# uctester.net
KiCad netlist of a schematic drawn in EAGLE
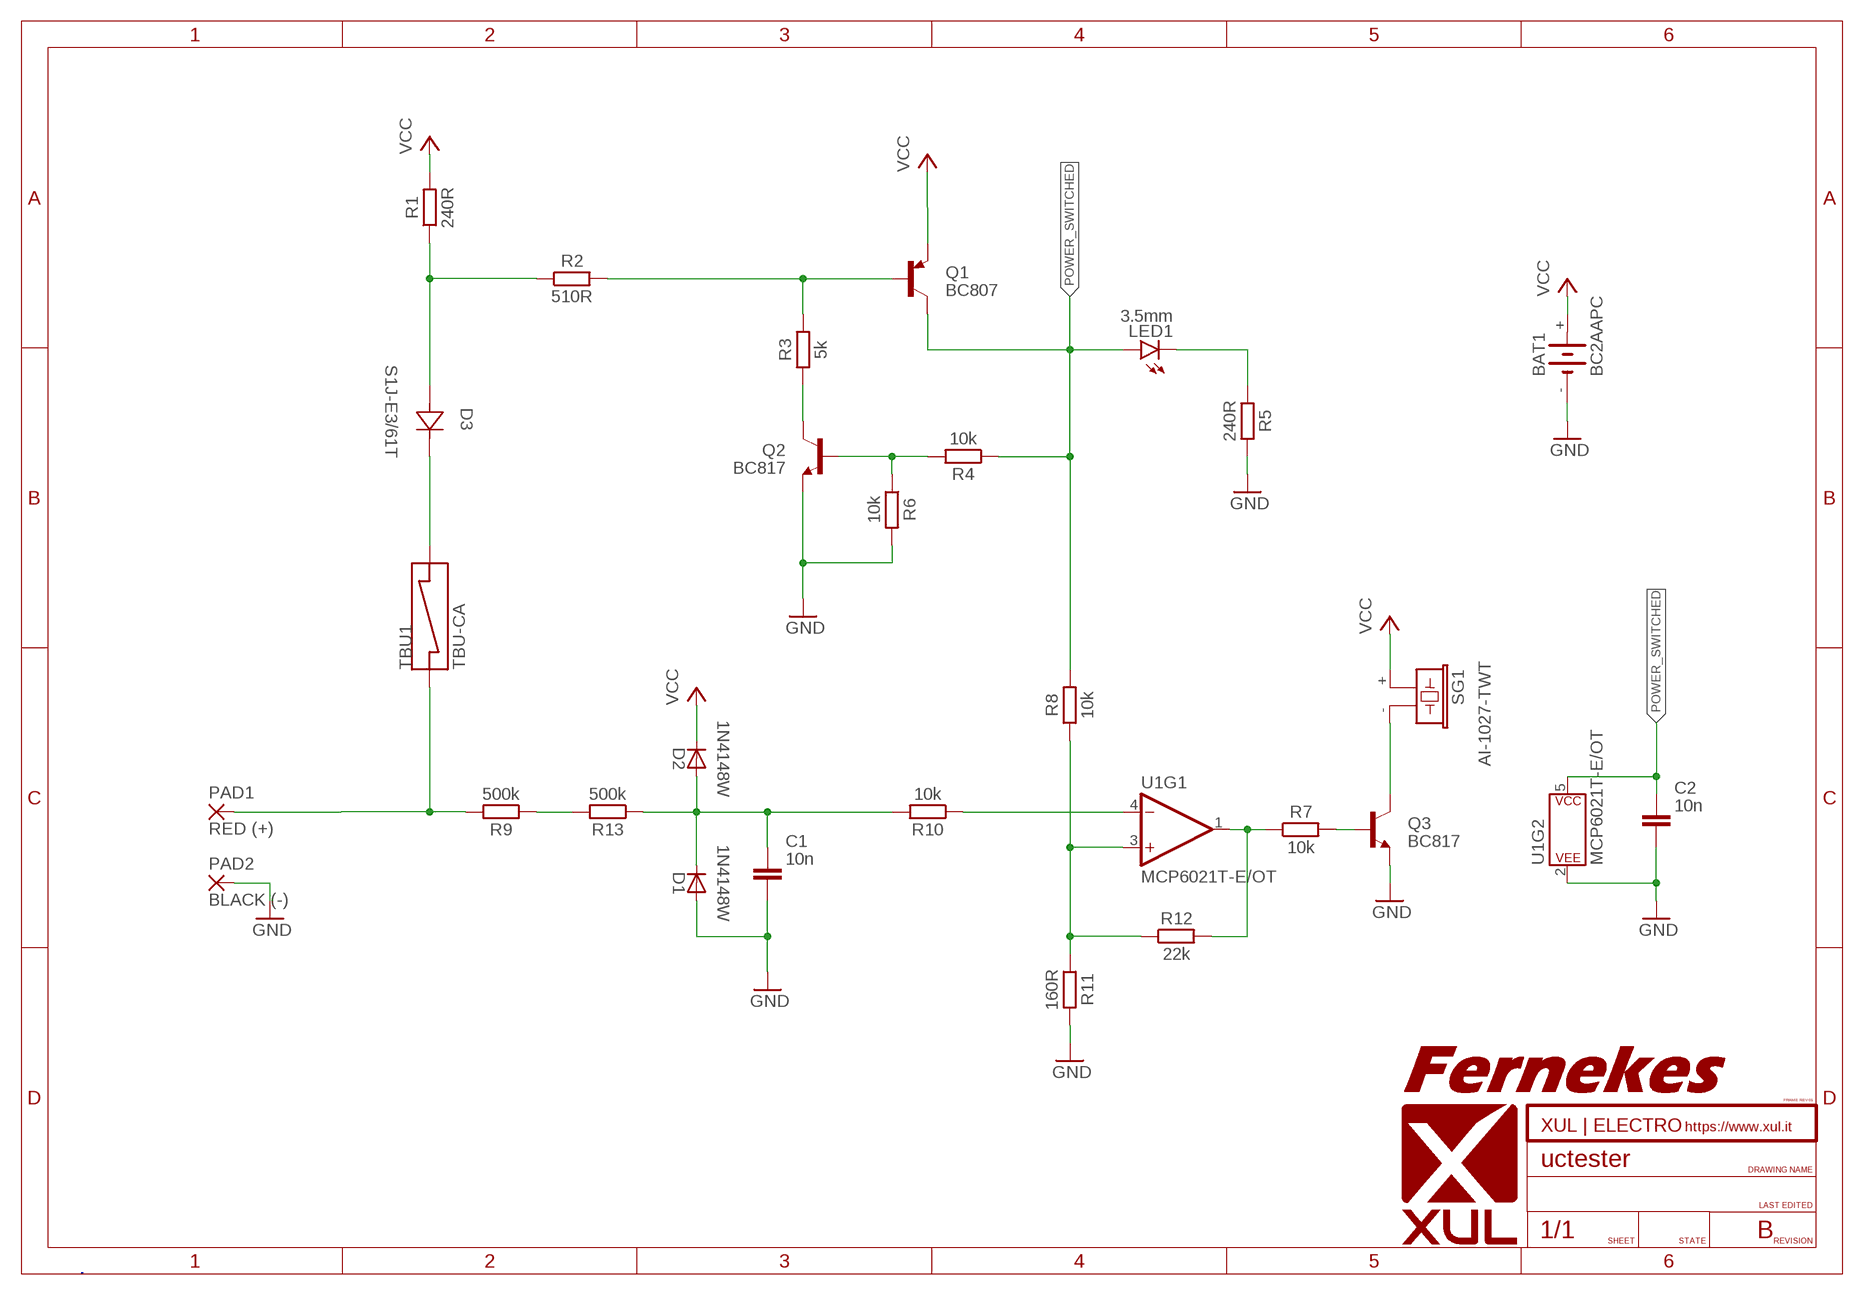
[diagram p0: schematic, sheet 1]

(export (version "E")
  (design (tool "Eeschema 10.0.6"))
  (components
    (comp (ref "BAT1")
      (value "BC2AAPC")
      (footprint "eagle-import:BC2AAPC")
      (libsource (lib "eagle-import") (part "BC2AAPC"))
    )
    (comp (ref "C1")
      (value "10n")
      (footprint "eagle-import:CAPC3216X135")
      (libsource (lib "eagle-import") (part "CCHIP-1206(3216-METRIC)_"))
    )
    (comp (ref "C2")
      (value "10n")
      (footprint "eagle-import:CAPC3216X135")
      (libsource (lib "eagle-import") (part "CCHIP-1206(3216-METRIC)_"))
    )
    (comp (ref "D1")
      (value "1N4148W")
      (footprint "eagle-import:SOD-123")
      (libsource (lib "eagle-import") (part "DIODESOD-123"))
    )
    (comp (ref "D2")
      (value "1N4148W")
      (footprint "eagle-import:SOD-123")
      (libsource (lib "eagle-import") (part "DIODESOD-123"))
    )
    (comp (ref "D3")
      (value "S1J-E3/61T")
      (footprint "eagle-import:DIODE_DO214AC")
      (libsource (lib "eagle-import") (part "S1J-E3/61T"))
    )
    (comp (ref "LED1")
      (value "3.5mm")
      (footprint "eagle-import:LED5MM")
      (libsource (lib "eagle-import") (part "LED5MM"))
    )
    (comp (ref "PAD1")
      (value "RED (+)")
      (footprint "eagle-import:SMD2,54-5,08")
      (libsource (lib "eagle-import") (part "WIREPADSMD2,54-5,08"))
    )
    (comp (ref "PAD2")
      (value "BLACK (-)")
      (footprint "eagle-import:SMD2,54-5,08")
      (libsource (lib "eagle-import") (part "WIREPADSMD2,54-5,08"))
    )
    (comp (ref "Q1")
      (value "BC807")
      (footprint "eagle-import:SOT23-BEC")
      (libsource (lib "eagle-import") (part "BC807SMD-40"))
    )
    (comp (ref "Q2")
      (value "BC817")
      (footprint "eagle-import:SOT23-BEC")
      (libsource (lib "eagle-import") (part "BC817SMD-40LT1"))
    )
    (comp (ref "Q3")
      (value "BC817")
      (footprint "eagle-import:SOT23-BEC")
      (libsource (lib "eagle-import") (part "BC817SMD-40LT1"))
    )
    (comp (ref "R1")
      (value "240R")
      (footprint "eagle-import:RESC3216X70")
      (libsource (lib "eagle-import") (part "RCHIP-1206(3216-METRIC)_"))
    )
    (comp (ref "R2")
      (value "510R")
      (footprint "eagle-import:RESC3216X70")
      (libsource (lib "eagle-import") (part "RCHIP-1206(3216-METRIC)_"))
    )
    (comp (ref "R3")
      (value "5k")
      (footprint "eagle-import:RESC3216X70")
      (libsource (lib "eagle-import") (part "RCHIP-1206(3216-METRIC)_"))
    )
    (comp (ref "R4")
      (value "10k")
      (footprint "eagle-import:RESC3216X70")
      (libsource (lib "eagle-import") (part "RCHIP-1206(3216-METRIC)_"))
    )
    (comp (ref "R5")
      (value "240R")
      (footprint "eagle-import:RESC3216X70")
      (libsource (lib "eagle-import") (part "RCHIP-1206(3216-METRIC)_"))
    )
    (comp (ref "R6")
      (value "10k")
      (footprint "eagle-import:RESC3216X70")
      (libsource (lib "eagle-import") (part "RCHIP-1206(3216-METRIC)_"))
    )
    (comp (ref "R7")
      (value "10k")
      (footprint "eagle-import:RESC3216X70")
      (libsource (lib "eagle-import") (part "RCHIP-1206(3216-METRIC)_"))
    )
    (comp (ref "R8")
      (value "10k")
      (footprint "eagle-import:RESC3216X70")
      (libsource (lib "eagle-import") (part "RCHIP-1206(3216-METRIC)_"))
    )
    (comp (ref "R9")
      (value "500k")
      (footprint "eagle-import:RESC3216X70")
      (libsource (lib "eagle-import") (part "RCHIP-1206(3216-METRIC)_"))
    )
    (comp (ref "R10")
      (value "10k")
      (footprint "eagle-import:RESC3216X70")
      (libsource (lib "eagle-import") (part "RCHIP-1206(3216-METRIC)_"))
    )
    (comp (ref "R11")
      (value "160R")
      (footprint "eagle-import:RESC3216X70")
      (libsource (lib "eagle-import") (part "RCHIP-1206(3216-METRIC)_"))
    )
    (comp (ref "R12")
      (value "22k")
      (footprint "eagle-import:RESC3216X70")
      (libsource (lib "eagle-import") (part "RCHIP-1206(3216-METRIC)_"))
    )
    (comp (ref "R13")
      (value "500k")
      (footprint "eagle-import:RESC3216X70")
      (libsource (lib "eagle-import") (part "RCHIP-1206(3216-METRIC)_"))
    )
    (comp (ref "SG1")
      (value "AI-1027-TWT")
      (footprint "eagle-import:AI-1027-TWT")
      (libsource (lib "eagle-import") (part "AI-1027-TWT"))
    )
    (comp (ref "TBU1")
      (value "TBU-CA")
      (footprint "eagle-import:RESDFN650X400X90-2N")
      (libsource (lib "eagle-import") (part "TBU-CA"))
    )
    (comp (ref "U1")
      (value "MCP6021T-E/OT")
      (footprint "eagle-import:SOT95P280X145-5N")
      (libsource (lib "eagle-import") (part "MCP6021T-E/OT"))
    )
  )
  (nets
    (net (code "1") (name "GND") (class "Default")
      (node (ref "BAT1") (pin "-") (pinfunction "-_-") (pintype "passive"))
      (node (ref "C1") (pin "2") (pinfunction "2_2") (pintype "passive"))
      (node (ref "C2") (pin "2") (pinfunction "2_2") (pintype "passive"))
      (node (ref "D1") (pin "A") (pinfunction "A_A") (pintype "passive"))
      (node (ref "PAD2") (pin "1") (pinfunction "P_1") (pintype "passive"))
      (node (ref "Q2") (pin "E") (pinfunction "E_E") (pintype "passive"))
      (node (ref "Q3") (pin "E") (pinfunction "E_E") (pintype "passive"))
      (node (ref "R11") (pin "2") (pinfunction "2_2") (pintype "passive"))
      (node (ref "R5") (pin "2") (pinfunction "2_2") (pintype "passive"))
      (node (ref "R6") (pin "2") (pinfunction "2_2") (pintype "passive"))
      (node (ref "U1") (pin "2") (pinfunction "P$V-_2") (pintype "bidirectional"))
    )
    (net (code "2") (name "Net-(C1-Pad1)") (class "Default")
      (node (ref "C1") (pin "1") (pinfunction "1_1") (pintype "passive"))
      (node (ref "D1") (pin "C") (pinfunction "C_C") (pintype "passive"))
      (node (ref "D2") (pin "A") (pinfunction "A_A") (pintype "passive"))
      (node (ref "R10") (pin "2") (pinfunction "2_2") (pintype "passive"))
      (node (ref "R13") (pin "1") (pinfunction "1_1") (pintype "passive"))
    )
    (net (code "3") (name "Net-(D3-A)") (class "Default")
      (node (ref "D3") (pin "2") (pinfunction "A_2") (pintype "passive"))
      (node (ref "R1") (pin "1") (pinfunction "1_1") (pintype "passive"))
      (node (ref "R2") (pin "1") (pinfunction "1_1") (pintype "passive"))
    )
    (net (code "4") (name "Net-(D3-C)") (class "Default")
      (node (ref "D3") (pin "1") (pinfunction "C_1") (pintype "passive"))
      (node (ref "TBU1") (pin "3") (pinfunction "P$2_3") (pintype "bidirectional"))
    )
    (net (code "5") (name "Net-(LED1-C)") (class "Default")
      (node (ref "LED1") (pin "K") (pinfunction "C_K") (pintype "passive"))
      (node (ref "R5") (pin "1") (pinfunction "1_1") (pintype "passive"))
    )
    (net (code "6") (name "Net-(PAD1-P)") (class "Default")
      (node (ref "PAD1") (pin "1") (pinfunction "P_1") (pintype "passive"))
      (node (ref "R9") (pin "2") (pinfunction "2_2") (pintype "passive"))
      (node (ref "TBU1") (pin "1") (pinfunction "P$1_1") (pintype "bidirectional"))
    )
    (net (code "7") (name "Net-(Q1-PadB)") (class "Default")
      (node (ref "Q1") (pin "B") (pinfunction "B_B") (pintype "passive"))
      (node (ref "R2") (pin "2") (pinfunction "2_2") (pintype "passive"))
      (node (ref "R3") (pin "2") (pinfunction "2_2") (pintype "passive"))
    )
    (net (code "8") (name "Net-(Q2-PadB)") (class "Default")
      (node (ref "Q2") (pin "B") (pinfunction "B_B") (pintype "passive"))
      (node (ref "R4") (pin "2") (pinfunction "2_2") (pintype "passive"))
      (node (ref "R6") (pin "1") (pinfunction "1_1") (pintype "passive"))
    )
    (net (code "9") (name "Net-(Q2-PadC)") (class "Default")
      (node (ref "Q2") (pin "C") (pinfunction "C_C") (pintype "passive"))
      (node (ref "R3") (pin "1") (pinfunction "1_1") (pintype "passive"))
    )
    (net (code "10") (name "Net-(Q3-PadB)") (class "Default")
      (node (ref "Q3") (pin "B") (pinfunction "B_B") (pintype "passive"))
      (node (ref "R7") (pin "2") (pinfunction "2_2") (pintype "passive"))
    )
    (net (code "11") (name "Net-(R13-Pad2)") (class "Default")
      (node (ref "R13") (pin "2") (pinfunction "2_2") (pintype "passive"))
      (node (ref "R9") (pin "1") (pinfunction "1_1") (pintype "passive"))
    )
    (net (code "12") (name "Net-(SG1-2)") (class "Default")
      (node (ref "Q3") (pin "C") (pinfunction "C_C") (pintype "passive"))
      (node (ref "SG1") (pin "-") (pinfunction "2_-") (pintype "passive"))
    )
    (net (code "13") (name "Net-(U1A-+IN)") (class "Default")
      (node (ref "R11") (pin "1") (pinfunction "1_1") (pintype "passive"))
      (node (ref "R12") (pin "1") (pinfunction "1_1") (pintype "passive"))
      (node (ref "R8") (pin "1") (pinfunction "1_1") (pintype "passive"))
      (node (ref "U1") (pin "3") (pinfunction "+IN_3") (pintype "input"))
    )
    (net (code "14") (name "Net-(U1A--IN)") (class "Default")
      (node (ref "R10") (pin "1") (pinfunction "1_1") (pintype "passive"))
      (node (ref "U1") (pin "4") (pinfunction "-IN_4") (pintype "input"))
    )
    (net (code "15") (name "Net-(U1A-OUT)") (class "Default")
      (node (ref "R12") (pin "2") (pinfunction "2_2") (pintype "passive"))
      (node (ref "R7") (pin "1") (pinfunction "1_1") (pintype "passive"))
      (node (ref "U1") (pin "1") (pinfunction "OUT_1") (pintype "output"))
    )
    (net (code "16") (name "POWER_SWITCHED") (class "Default")
      (node (ref "C2") (pin "1") (pinfunction "1_1") (pintype "passive"))
      (node (ref "LED1") (pin "A") (pinfunction "A_A") (pintype "passive"))
      (node (ref "Q1") (pin "C") (pinfunction "C_C") (pintype "passive"))
      (node (ref "R4") (pin "1") (pinfunction "1_1") (pintype "passive"))
      (node (ref "R8") (pin "2") (pinfunction "2_2") (pintype "passive"))
      (node (ref "U1") (pin "5") (pinfunction "P$V+_5") (pintype "bidirectional"))
    )
    (net (code "17") (name "VCC") (class "Default")
      (node (ref "BAT1") (pin "+") (pinfunction "+_+") (pintype "passive"))
      (node (ref "D2") (pin "C") (pinfunction "C_C") (pintype "passive"))
      (node (ref "Q1") (pin "E") (pinfunction "E_E") (pintype "passive"))
      (node (ref "R1") (pin "2") (pinfunction "2_2") (pintype "passive"))
      (node (ref "SG1") (pin "+") (pinfunction "1_+") (pintype "passive"))
    )
  )
)
